# Organ.net
KiCad netlist of a schematic drawn in EAGLE
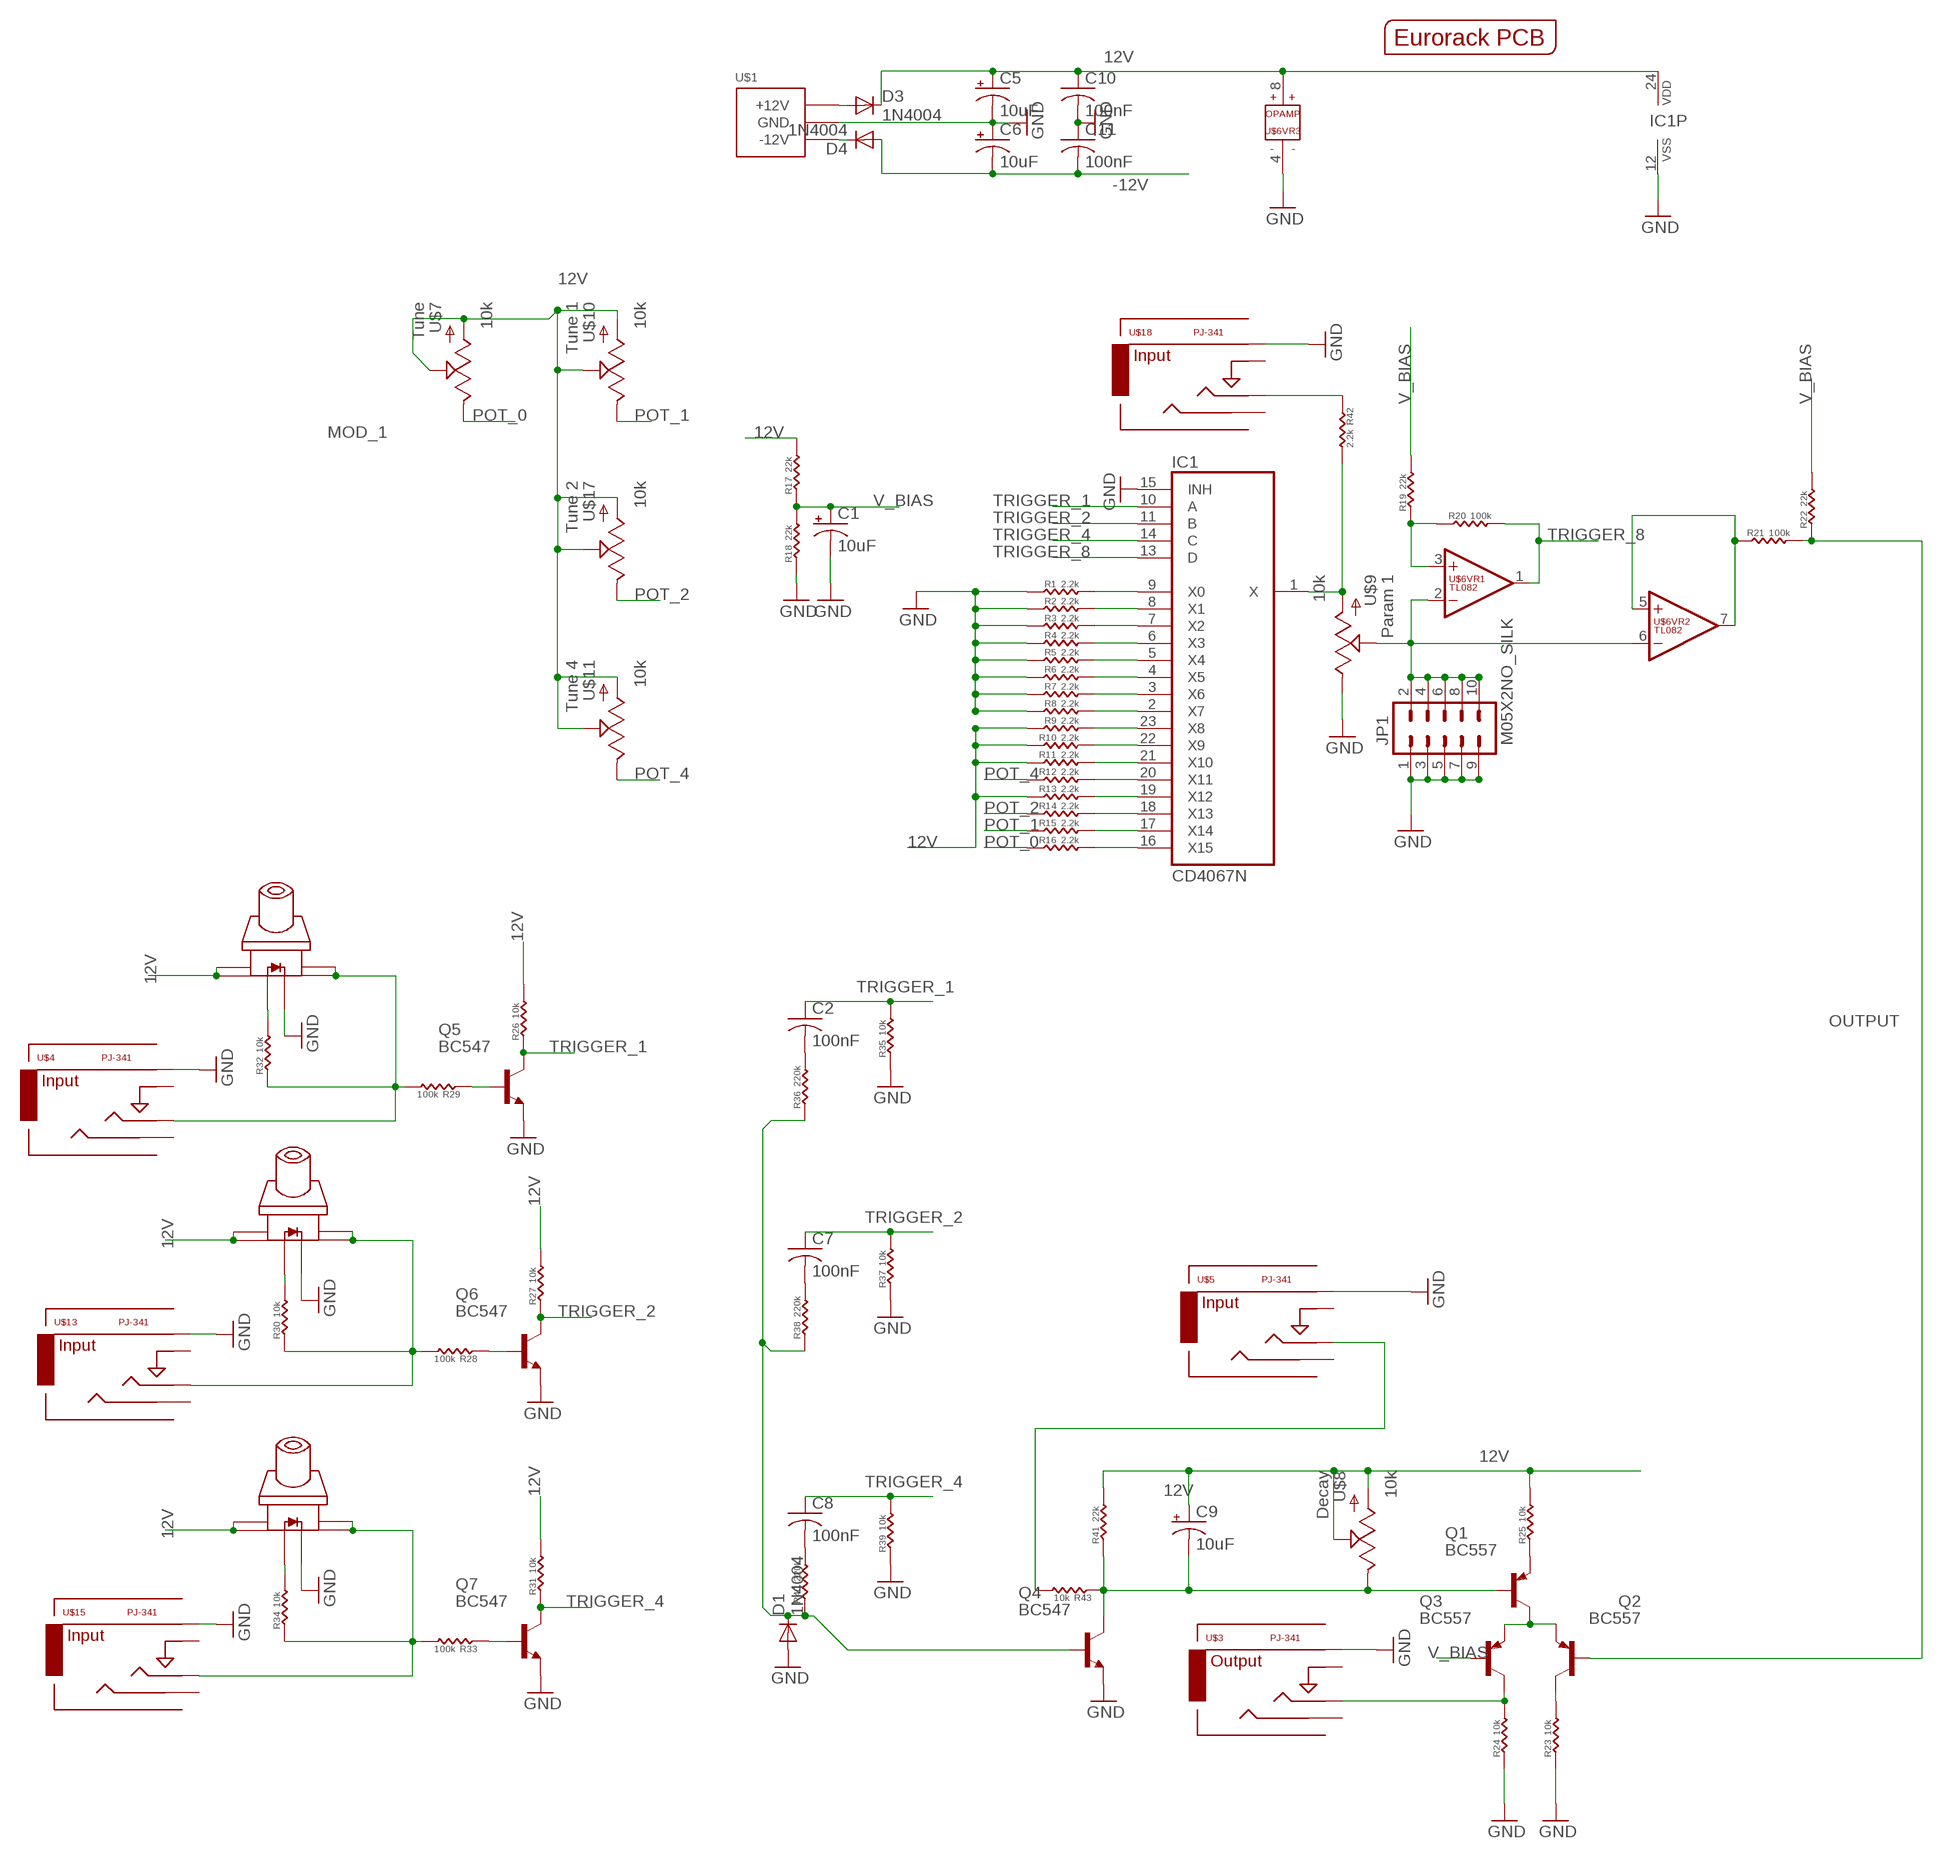
[diagram p0: schematic, sheet 1]

(export (version "E")
  (design (tool "Eeschema 10.0.6"))
  (components
    (comp (ref "C1")
      (value "10uF")
      (footprint "eagle-import:E5-6")
      (libsource (lib "eagle-import") (part "CPOL-USE5-6"))
    )
    (comp (ref "C2")
      (value "100nF")
      (footprint "eagle-import:C050-025X075")
      (libsource (lib "eagle-import") (part "C-US050-025X075"))
    )
    (comp (ref "C5")
      (value "10uF")
      (footprint "eagle-import:E5-6")
      (libsource (lib "eagle-import") (part "CPOL-USE5-6"))
    )
    (comp (ref "C6")
      (value "10uF")
      (footprint "eagle-import:E5-6")
      (libsource (lib "eagle-import") (part "CPOL-USE5-6"))
    )
    (comp (ref "C7")
      (value "100nF")
      (footprint "eagle-import:C050-025X075")
      (libsource (lib "eagle-import") (part "C-US050-025X075"))
    )
    (comp (ref "C8")
      (value "100nF")
      (footprint "eagle-import:C050-025X075")
      (libsource (lib "eagle-import") (part "C-US050-025X075"))
    )
    (comp (ref "C9")
      (value "10uF")
      (footprint "eagle-import:E5-6")
      (libsource (lib "eagle-import") (part "CPOL-USE5-6"))
    )
    (comp (ref "C10")
      (value "100nF")
      (footprint "eagle-import:C050-025X075")
      (libsource (lib "eagle-import") (part "C-US050-025X075"))
    )
    (comp (ref "C11")
      (value "100nF")
      (footprint "eagle-import:C050-025X075")
      (libsource (lib "eagle-import") (part "C-US050-025X075"))
    )
    (comp (ref "D1")
      (value "1N4004")
      (footprint "eagle-import:DO41-10")
      (libsource (lib "eagle-import") (part "1N4004"))
    )
    (comp (ref "D3")
      (value "1N4004")
      (footprint "eagle-import:DO41-10")
      (libsource (lib "eagle-import") (part "1N4004"))
    )
    (comp (ref "D4")
      (value "1N4004")
      (footprint "eagle-import:DO41-10")
      (libsource (lib "eagle-import") (part "1N4004"))
    )
    (comp (ref "IC1")
      (value "CD4067N")
      (footprint "eagle-import:DIL24-6")
      (libsource (lib "eagle-import") (part "4067N"))
    )
    (comp (ref "JP1")
      (value "M05X2NO_SILK")
      (footprint "eagle-import:2X5_NOSILK")
      (libsource (lib "eagle-import") (part "M05X2NO_SILK"))
    )
    (comp (ref "Q1")
      (value "BC557")
      (footprint "eagle-import:TO92")
      (libsource (lib "eagle-import") (part "BC557TO92"))
    )
    (comp (ref "Q2")
      (value "BC557")
      (footprint "eagle-import:TO92")
      (libsource (lib "eagle-import") (part "BC557TO92"))
    )
    (comp (ref "Q3")
      (value "BC557")
      (footprint "eagle-import:TO92")
      (libsource (lib "eagle-import") (part "BC557TO92"))
    )
    (comp (ref "Q4")
      (value "BC547")
      (footprint "eagle-import:TO92")
      (libsource (lib "eagle-import") (part "BC547"))
    )
    (comp (ref "Q5")
      (value "BC547")
      (footprint "eagle-import:TO92")
      (libsource (lib "eagle-import") (part "BC547"))
    )
    (comp (ref "Q6")
      (value "BC547")
      (footprint "eagle-import:TO92")
      (libsource (lib "eagle-import") (part "BC547"))
    )
    (comp (ref "Q7")
      (value "BC547")
      (footprint "eagle-import:TO92")
      (libsource (lib "eagle-import") (part "BC547"))
    )
    (comp (ref "R1")
      (value "2.2k")
      (footprint "eagle-import:0204_5")
      (libsource (lib "eagle-import") (part "R-US_0204/5"))
    )
    (comp (ref "R2")
      (value "2.2k")
      (footprint "eagle-import:0204_5")
      (libsource (lib "eagle-import") (part "R-US_0204/5"))
    )
    (comp (ref "R3")
      (value "2.2k")
      (footprint "eagle-import:0204_5")
      (libsource (lib "eagle-import") (part "R-US_0204/5"))
    )
    (comp (ref "R4")
      (value "2.2k")
      (footprint "eagle-import:0204_5")
      (libsource (lib "eagle-import") (part "R-US_0204/5"))
    )
    (comp (ref "R5")
      (value "2.2k")
      (footprint "eagle-import:0204_5")
      (libsource (lib "eagle-import") (part "R-US_0204/5"))
    )
    (comp (ref "R6")
      (value "2.2k")
      (footprint "eagle-import:0204_5")
      (libsource (lib "eagle-import") (part "R-US_0204/5"))
    )
    (comp (ref "R7")
      (value "2.2k")
      (footprint "eagle-import:0204_5")
      (libsource (lib "eagle-import") (part "R-US_0204/5"))
    )
    (comp (ref "R8")
      (value "2.2k")
      (footprint "eagle-import:0204_5")
      (libsource (lib "eagle-import") (part "R-US_0204/5"))
    )
    (comp (ref "R9")
      (value "2.2k")
      (footprint "eagle-import:0204_5")
      (libsource (lib "eagle-import") (part "R-US_0204/5"))
    )
    (comp (ref "R10")
      (value "2.2k")
      (footprint "eagle-import:0204_5")
      (libsource (lib "eagle-import") (part "R-US_0204/5"))
    )
    (comp (ref "R11")
      (value "2.2k")
      (footprint "eagle-import:0204_5")
      (libsource (lib "eagle-import") (part "R-US_0204/5"))
    )
    (comp (ref "R12")
      (value "2.2k")
      (footprint "eagle-import:0204_5")
      (libsource (lib "eagle-import") (part "R-US_0204/5"))
    )
    (comp (ref "R13")
      (value "2.2k")
      (footprint "eagle-import:0204_5")
      (libsource (lib "eagle-import") (part "R-US_0204/5"))
    )
    (comp (ref "R14")
      (value "2.2k")
      (footprint "eagle-import:0204_5")
      (libsource (lib "eagle-import") (part "R-US_0204/5"))
    )
    (comp (ref "R15")
      (value "2.2k")
      (footprint "eagle-import:0204_5")
      (libsource (lib "eagle-import") (part "R-US_0204/5"))
    )
    (comp (ref "R16")
      (value "2.2k")
      (footprint "eagle-import:0204_5")
      (libsource (lib "eagle-import") (part "R-US_0204/5"))
    )
    (comp (ref "R17")
      (value "22k")
      (footprint "eagle-import:0204_5")
      (libsource (lib "eagle-import") (part "R-US_0204/5"))
    )
    (comp (ref "R18")
      (value "22k")
      (footprint "eagle-import:0204_5")
      (libsource (lib "eagle-import") (part "R-US_0204/5"))
    )
    (comp (ref "R19")
      (value "22k")
      (footprint "eagle-import:0204_5")
      (libsource (lib "eagle-import") (part "R-US_0204/5"))
    )
    (comp (ref "R20")
      (value "100k")
      (footprint "eagle-import:0204_5")
      (libsource (lib "eagle-import") (part "R-US_0204/5"))
    )
    (comp (ref "R21")
      (value "100k")
      (footprint "eagle-import:0204_5")
      (libsource (lib "eagle-import") (part "R-US_0204/5"))
    )
    (comp (ref "R22")
      (value "22k")
      (footprint "eagle-import:0204_5")
      (libsource (lib "eagle-import") (part "R-US_0204/5"))
    )
    (comp (ref "R23")
      (value "10k")
      (footprint "eagle-import:0204_5")
      (libsource (lib "eagle-import") (part "R-US_0204/5"))
    )
    (comp (ref "R24")
      (value "10k")
      (footprint "eagle-import:0204_5")
      (libsource (lib "eagle-import") (part "R-US_0204/5"))
    )
    (comp (ref "R25")
      (value "10k")
      (footprint "eagle-import:0204_5")
      (libsource (lib "eagle-import") (part "R-US_0204/5"))
    )
    (comp (ref "R26")
      (value "10k")
      (footprint "eagle-import:0204_5")
      (libsource (lib "eagle-import") (part "R-US_0204/5"))
    )
    (comp (ref "R27")
      (value "10k")
      (footprint "eagle-import:0204_5")
      (libsource (lib "eagle-import") (part "R-US_0204/5"))
    )
    (comp (ref "R28")
      (value "100k")
      (footprint "eagle-import:0204_5")
      (libsource (lib "eagle-import") (part "R-US_0204/5"))
    )
    (comp (ref "R29")
      (value "100k")
      (footprint "eagle-import:0204_5")
      (libsource (lib "eagle-import") (part "R-US_0204/5"))
    )
    (comp (ref "R30")
      (value "10k")
      (footprint "eagle-import:0204_5")
      (libsource (lib "eagle-import") (part "R-US_0204/5"))
    )
    (comp (ref "R31")
      (value "10k")
      (footprint "eagle-import:0204_5")
      (libsource (lib "eagle-import") (part "R-US_0204/5"))
    )
    (comp (ref "R32")
      (value "10k")
      (footprint "eagle-import:0204_5")
      (libsource (lib "eagle-import") (part "R-US_0204/5"))
    )
    (comp (ref "R33")
      (value "100k")
      (footprint "eagle-import:0204_5")
      (libsource (lib "eagle-import") (part "R-US_0204/5"))
    )
    (comp (ref "R34")
      (value "10k")
      (footprint "eagle-import:0204_5")
      (libsource (lib "eagle-import") (part "R-US_0204/5"))
    )
    (comp (ref "R35")
      (value "10k")
      (footprint "eagle-import:0204_5")
      (libsource (lib "eagle-import") (part "R-US_0204/5"))
    )
    (comp (ref "R36")
      (value "220k")
      (footprint "eagle-import:0204_5")
      (libsource (lib "eagle-import") (part "R-US_0204/5"))
    )
    (comp (ref "R37")
      (value "10k")
      (footprint "eagle-import:0204_5")
      (libsource (lib "eagle-import") (part "R-US_0204/5"))
    )
    (comp (ref "R38")
      (value "220k")
      (footprint "eagle-import:0204_5")
      (libsource (lib "eagle-import") (part "R-US_0204/5"))
    )
    (comp (ref "R39")
      (value "10k")
      (footprint "eagle-import:0204_5")
      (libsource (lib "eagle-import") (part "R-US_0204/5"))
    )
    (comp (ref "R40")
      (value "220k")
      (footprint "eagle-import:0204_5")
      (libsource (lib "eagle-import") (part "R-US_0204/5"))
    )
    (comp (ref "R41")
      (value "22k")
      (footprint "eagle-import:0204_5")
      (libsource (lib "eagle-import") (part "R-US_0204/5"))
    )
    (comp (ref "R42")
      (value "2.2k")
      (footprint "eagle-import:0204_5")
      (libsource (lib "eagle-import") (part "R-US_0204/5"))
    )
    (comp (ref "R43")
      (value "10k")
      (footprint "eagle-import:0204_5")
      (libsource (lib "eagle-import") (part "R-US_0204/5"))
    )
    (comp (ref "U$1")
      (value "POWER_SIMPLE10")
      (footprint "eagle-import:POWER_10")
      (libsource (lib "eagle-import") (part "POWER_SIMPLE10"))
    )
    (comp (ref "U$2")
      (value "EURORACK_PCB12HP")
      (footprint "eagle-import:EURORACK12HPPCB")
      (libsource (lib "eagle-import") (part "EURORACK_PCB12HP"))
    )
    (comp (ref "U$3")
      (value "PJ-341")
      (footprint "eagle-import:3.5MM-JACK-SWITCH-13MM-OUTPUT")
      (libsource (lib "eagle-import") (part "AUDIO-JACKOUTPUT"))
    )
    (comp (ref "U$4")
      (value "PJ-341")
      (footprint "eagle-import:3.5MM-JACK-SWITCH-13MM-INPUT")
      (libsource (lib "eagle-import") (part "AUDIO-JACKINPUT"))
    )
    (comp (ref "U$5")
      (value "PJ-341")
      (footprint "eagle-import:3.5MM-JACK-SWITCH-13MM-INPUT")
      (libsource (lib "eagle-import") (part "AUDIO-JACKINPUT"))
    )
    (comp (ref "U$6")
      (value "TL082")
      (footprint "eagle-import:DIL08")
      (libsource (lib "eagle-import") (part "TL072DIP"))
    )
    (comp (ref "U$7")
      (value "10k")
      (footprint "eagle-import:OG-POTS_ALPS_POT_VERTICAL")
      (fields (field (name "DESC") "Tune"))
      (libsource (lib "eagle-import") (part "POTZEPHPOT"))
    )
    (comp (ref "U$8")
      (value "10k")
      (footprint "eagle-import:OG-POTS_ALPS_POT_VERTICAL")
      (fields (field (name "DESC") "Decay"))
      (libsource (lib "eagle-import") (part "POTZEPHPOT"))
    )
    (comp (ref "U$9")
      (value "10k")
      (footprint "eagle-import:OG-POTS_ALPS_POT_VERTICAL")
      (fields (field (name "DESC") "Param 1"))
      (libsource (lib "eagle-import") (part "POTZEPHPOT"))
    )
    (comp (ref "U$10")
      (value "10k")
      (footprint "eagle-import:OG-POTS_ALPS_POT_VERTICAL")
      (fields (field (name "DESC") "Tune 1"))
      (libsource (lib "eagle-import") (part "POTZEPHPOT"))
    )
    (comp (ref "U$11")
      (value "10k")
      (footprint "eagle-import:OG-POTS_ALPS_POT_VERTICAL")
      (fields (field (name "DESC") "Tune 4"))
      (libsource (lib "eagle-import") (part "POTZEPHPOT"))
    )
    (comp (ref "U$12")
      (value "SWITCH_W_LED_PB6149L-X-102YELLOW")
      (footprint "eagle-import:PB6149L")
      (libsource (lib "eagle-import") (part "SWITCH_W_LED_PB6149L-X-102YELLOW"))
    )
    (comp (ref "U$13")
      (value "PJ-341")
      (footprint "eagle-import:3.5MM-JACK-SWITCH-13MM-INPUT")
      (libsource (lib "eagle-import") (part "AUDIO-JACKINPUT"))
    )
    (comp (ref "U$14")
      (value "SWITCH_W_LED_PB6149L-X-102YELLOW")
      (footprint "eagle-import:PB6149L")
      (libsource (lib "eagle-import") (part "SWITCH_W_LED_PB6149L-X-102YELLOW"))
    )
    (comp (ref "U$15")
      (value "PJ-341")
      (footprint "eagle-import:3.5MM-JACK-SWITCH-13MM-INPUT")
      (libsource (lib "eagle-import") (part "AUDIO-JACKINPUT"))
    )
    (comp (ref "U$16")
      (value "SWITCH_W_LED_PB6149L-X-102YELLOW")
      (footprint "eagle-import:PB6149L")
      (libsource (lib "eagle-import") (part "SWITCH_W_LED_PB6149L-X-102YELLOW"))
    )
    (comp (ref "U$17")
      (value "10k")
      (footprint "eagle-import:OG-POTS_ALPS_POT_VERTICAL")
      (fields (field (name "DESC") "Tune 2"))
      (libsource (lib "eagle-import") (part "POTZEPHPOT"))
    )
    (comp (ref "U$18")
      (value "PJ-341")
      (footprint "eagle-import:3.5MM-JACK-SWITCH-13MM-INPUT")
      (libsource (lib "eagle-import") (part "AUDIO-JACKINPUT"))
    )
  )
  (nets
    (net (code "1") (name "/-12V") (class "Default")
      (node (ref "C11") (pin "2") (pinfunction "2_2") (pintype "passive"))
      (node (ref "C6") (pin "-") (pinfunction "-_-") (pintype "passive"))
      (node (ref "D4") (pin "A") (pinfunction "A_A") (pintype "passive"))
    )
    (net (code "2") (name "/12V") (class "Default")
      (node (ref "C10") (pin "1") (pinfunction "1_1") (pintype "passive"))
      (node (ref "C5") (pin "+") (pinfunction "+_+") (pintype "passive"))
      (node (ref "C9") (pin "+") (pinfunction "+_+") (pintype "passive"))
      (node (ref "D3") (pin "C") (pinfunction "C_C") (pintype "passive"))
      (node (ref "IC1") (pin "24") (pinfunction "VDD_24") (pintype "power_in"))
      (node (ref "R10") (pin "1") (pinfunction "1_1") (pintype "passive"))
      (node (ref "R11") (pin "1") (pinfunction "1_1") (pintype "passive"))
      (node (ref "R13") (pin "1") (pinfunction "1_1") (pintype "passive"))
      (node (ref "R17") (pin "2") (pinfunction "2_2") (pintype "passive"))
      (node (ref "R25") (pin "2") (pinfunction "2_2") (pintype "passive"))
      (node (ref "R26") (pin "2") (pinfunction "2_2") (pintype "passive"))
      (node (ref "R27") (pin "2") (pinfunction "2_2") (pintype "passive"))
      (node (ref "R31") (pin "2") (pinfunction "2_2") (pintype "passive"))
      (node (ref "R41") (pin "2") (pinfunction "2_2") (pintype "passive"))
      (node (ref "R9") (pin "1") (pinfunction "1_1") (pintype "passive"))
      (node (ref "U$10") (pin "P$2") (pinfunction "S_P$2") (pintype "passive"))
      (node (ref "U$10") (pin "P$3") (pinfunction "A_P$3") (pintype "passive"))
      (node (ref "U$11") (pin "P$2") (pinfunction "S_P$2") (pintype "passive"))
      (node (ref "U$11") (pin "P$3") (pinfunction "A_P$3") (pintype "passive"))
      (node (ref "U$12") (pin "1") (pinfunction "1_1") (pintype "bidirectional"))
      (node (ref "U$12") (pin "2") (pinfunction "2_2") (pintype "bidirectional"))
      (node (ref "U$14") (pin "1") (pinfunction "1_1") (pintype "bidirectional"))
      (node (ref "U$14") (pin "2") (pinfunction "2_2") (pintype "bidirectional"))
      (node (ref "U$16") (pin "1") (pinfunction "1_1") (pintype "bidirectional"))
      (node (ref "U$16") (pin "2") (pinfunction "2_2") (pintype "bidirectional"))
      (node (ref "U$17") (pin "P$2") (pinfunction "S_P$2") (pintype "passive"))
      (node (ref "U$17") (pin "P$3") (pinfunction "A_P$3") (pintype "passive"))
      (node (ref "U$6") (pin "8") (pinfunction "V+_8") (pintype "power_in"))
      (node (ref "U$7") (pin "P$2") (pinfunction "S_P$2") (pintype "passive"))
      (node (ref "U$7") (pin "P$3") (pinfunction "A_P$3") (pintype "passive"))
      (node (ref "U$8") (pin "P$2") (pinfunction "S_P$2") (pintype "passive"))
      (node (ref "U$8") (pin "P$3") (pinfunction "A_P$3") (pintype "passive"))
    )
    (net (code "3") (name "/MOD_1") (class "Default")
      (node (ref "IC1") (pin "1") (pinfunction "X_1") (pintype "output"))
      (node (ref "R42") (pin "2") (pinfunction "2_2") (pintype "passive"))
      (node (ref "U$9") (pin "P$3") (pinfunction "A_P$3") (pintype "passive"))
    )
    (net (code "4") (name "/OUTPUT") (class "Default")
      (node (ref "Q2") (pin "2") (pinfunction "B_2") (pintype "passive"))
      (node (ref "R21") (pin "2") (pinfunction "2_2") (pintype "passive"))
      (node (ref "R22") (pin "1") (pinfunction "1_1") (pintype "passive"))
    )
    (net (code "5") (name "/POT_0") (class "Default")
      (node (ref "R16") (pin "1") (pinfunction "1_1") (pintype "passive"))
      (node (ref "U$7") (pin "P$1") (pinfunction "E_P$1") (pintype "passive"))
    )
    (net (code "6") (name "/POT_1") (class "Default")
      (node (ref "R15") (pin "1") (pinfunction "1_1") (pintype "passive"))
      (node (ref "U$10") (pin "P$1") (pinfunction "E_P$1") (pintype "passive"))
    )
    (net (code "7") (name "/POT_2") (class "Default")
      (node (ref "R14") (pin "1") (pinfunction "1_1") (pintype "passive"))
      (node (ref "U$17") (pin "P$1") (pinfunction "E_P$1") (pintype "passive"))
    )
    (net (code "8") (name "/POT_4") (class "Default")
      (node (ref "R12") (pin "1") (pinfunction "1_1") (pintype "passive"))
      (node (ref "U$11") (pin "P$1") (pinfunction "E_P$1") (pintype "passive"))
    )
    (net (code "9") (name "/TRIGGER_1") (class "Default")
      (node (ref "C2") (pin "1") (pinfunction "1_1") (pintype "passive"))
      (node (ref "IC1") (pin "10") (pinfunction "A_10") (pintype "input"))
      (node (ref "Q5") (pin "3") (pinfunction "C_3") (pintype "passive"))
      (node (ref "R26") (pin "1") (pinfunction "1_1") (pintype "passive"))
      (node (ref "R35") (pin "2") (pinfunction "2_2") (pintype "passive"))
    )
    (net (code "10") (name "/TRIGGER_2") (class "Default")
      (node (ref "C7") (pin "1") (pinfunction "1_1") (pintype "passive"))
      (node (ref "IC1") (pin "11") (pinfunction "B_11") (pintype "input"))
      (node (ref "Q6") (pin "3") (pinfunction "C_3") (pintype "passive"))
      (node (ref "R27") (pin "1") (pinfunction "1_1") (pintype "passive"))
      (node (ref "R37") (pin "2") (pinfunction "2_2") (pintype "passive"))
    )
    (net (code "11") (name "/TRIGGER_4") (class "Default")
      (node (ref "C8") (pin "1") (pinfunction "1_1") (pintype "passive"))
      (node (ref "IC1") (pin "14") (pinfunction "C_14") (pintype "input"))
      (node (ref "Q7") (pin "3") (pinfunction "C_3") (pintype "passive"))
      (node (ref "R31") (pin "1") (pinfunction "1_1") (pintype "passive"))
      (node (ref "R39") (pin "2") (pinfunction "2_2") (pintype "passive"))
    )
    (net (code "12") (name "/TRIGGER_8") (class "Default")
      (node (ref "IC1") (pin "13") (pinfunction "D_13") (pintype "input"))
      (node (ref "R20") (pin "2") (pinfunction "2_2") (pintype "passive"))
      (node (ref "U$6") (pin "1") (pinfunction "OUT_1") (pintype "output"))
    )
    (net (code "13") (name "/V_BIAS") (class "Default")
      (node (ref "C1") (pin "+") (pinfunction "+_+") (pintype "passive"))
      (node (ref "Q3") (pin "2") (pinfunction "B_2") (pintype "passive"))
      (node (ref "R17") (pin "1") (pinfunction "1_1") (pintype "passive"))
      (node (ref "R18") (pin "2") (pinfunction "2_2") (pintype "passive"))
      (node (ref "R19") (pin "2") (pinfunction "2_2") (pintype "passive"))
      (node (ref "R22") (pin "2") (pinfunction "2_2") (pintype "passive"))
    )
    (net (code "14") (name "GND") (class "Default")
      (node (ref "C1") (pin "-") (pinfunction "-_-") (pintype "passive"))
      (node (ref "C10") (pin "2") (pinfunction "2_2") (pintype "passive"))
      (node (ref "C11") (pin "1") (pinfunction "1_1") (pintype "passive"))
      (node (ref "C5") (pin "-") (pinfunction "-_-") (pintype "passive"))
      (node (ref "C6") (pin "+") (pinfunction "+_+") (pintype "passive"))
      (node (ref "D1") (pin "A") (pinfunction "A_A") (pintype "passive"))
      (node (ref "IC1") (pin "12") (pinfunction "VSS_12") (pintype "power_in"))
      (node (ref "IC1") (pin "15") (pinfunction "INH_15") (pintype "input"))
      (node (ref "JP1") (pin "1") (pinfunction "1_1") (pintype "passive"))
      (node (ref "JP1") (pin "3") (pinfunction "3_3") (pintype "passive"))
      (node (ref "JP1") (pin "5") (pinfunction "5_5") (pintype "passive"))
      (node (ref "JP1") (pin "7") (pinfunction "7_7") (pintype "passive"))
      (node (ref "JP1") (pin "9") (pinfunction "9_9") (pintype "passive"))
      (node (ref "Q4") (pin "1") (pinfunction "E_1") (pintype "passive"))
      (node (ref "Q5") (pin "1") (pinfunction "E_1") (pintype "passive"))
      (node (ref "Q6") (pin "1") (pinfunction "E_1") (pintype "passive"))
      (node (ref "Q7") (pin "1") (pinfunction "E_1") (pintype "passive"))
      (node (ref "R1") (pin "1") (pinfunction "1_1") (pintype "passive"))
      (node (ref "R18") (pin "1") (pinfunction "1_1") (pintype "passive"))
      (node (ref "R2") (pin "1") (pinfunction "1_1") (pintype "passive"))
      (node (ref "R23") (pin "1") (pinfunction "1_1") (pintype "passive"))
      (node (ref "R24") (pin "1") (pinfunction "1_1") (pintype "passive"))
      (node (ref "R3") (pin "1") (pinfunction "1_1") (pintype "passive"))
      (node (ref "R35") (pin "1") (pinfunction "1_1") (pintype "passive"))
      (node (ref "R37") (pin "1") (pinfunction "1_1") (pintype "passive"))
      (node (ref "R39") (pin "1") (pinfunction "1_1") (pintype "passive"))
      (node (ref "R4") (pin "1") (pinfunction "1_1") (pintype "passive"))
      (node (ref "R5") (pin "1") (pinfunction "1_1") (pintype "passive"))
      (node (ref "R6") (pin "1") (pinfunction "1_1") (pintype "passive"))
      (node (ref "R7") (pin "1") (pinfunction "1_1") (pintype "passive"))
      (node (ref "R8") (pin "1") (pinfunction "1_1") (pintype "passive"))
      (node (ref "U$1") (pin "3") (pinfunction "GND_3") (pintype "bidirectional"))
      (node (ref "U$1") (pin "4") (pinfunction "GND_4") (pintype "bidirectional"))
      (node (ref "U$1") (pin "5") (pinfunction "GND_5") (pintype "bidirectional"))
      (node (ref "U$1") (pin "6") (pinfunction "GND_6") (pintype "bidirectional"))
      (node (ref "U$1") (pin "7") (pinfunction "GND_7") (pintype "bidirectional"))
      (node (ref "U$1") (pin "8") (pinfunction "GND_8") (pintype "bidirectional"))
      (node (ref "U$12") (pin "LEDNEG") (pinfunction "NEG_LEDNEG") (pintype "bidirectional"))
      (node (ref "U$13") (pin "RING@3") (pinfunction "RING_RING@3") (pintype "bidirectional"))
      (node (ref "U$14") (pin "LEDNEG") (pinfunction "NEG_LEDNEG") (pintype "bidirectional"))
      (node (ref "U$15") (pin "RING@3") (pinfunction "RING_RING@3") (pintype "bidirectional"))
      (node (ref "U$16") (pin "LEDNEG") (pinfunction "NEG_LEDNEG") (pintype "bidirectional"))
      (node (ref "U$18") (pin "RING@3") (pinfunction "RING_RING@3") (pintype "bidirectional"))
      (node (ref "U$3") (pin "RING@3") (pinfunction "RING_RING@3") (pintype "bidirectional"))
      (node (ref "U$4") (pin "RING@3") (pinfunction "RING_RING@3") (pintype "bidirectional"))
      (node (ref "U$5") (pin "RING@3") (pinfunction "RING_RING@3") (pintype "bidirectional"))
      (node (ref "U$6") (pin "4") (pinfunction "V-_4") (pintype "power_in"))
      (node (ref "U$9") (pin "P$1") (pinfunction "E_P$1") (pintype "passive"))
    )
    (net (code "15") (name "Net-(C2-Pad2)") (class "Default")
      (node (ref "C2") (pin "2") (pinfunction "2_2") (pintype "passive"))
      (node (ref "R36") (pin "2") (pinfunction "2_2") (pintype "passive"))
    )
    (net (code "16") (name "Net-(C7-Pad2)") (class "Default")
      (node (ref "C7") (pin "2") (pinfunction "2_2") (pintype "passive"))
      (node (ref "R38") (pin "2") (pinfunction "2_2") (pintype "passive"))
    )
    (net (code "17") (name "Net-(C8-Pad2)") (class "Default")
      (node (ref "C8") (pin "2") (pinfunction "2_2") (pintype "passive"))
      (node (ref "R40") (pin "2") (pinfunction "2_2") (pintype "passive"))
    )
    (net (code "18") (name "Net-(D3-PadA)") (class "Default")
      (node (ref "D3") (pin "A") (pinfunction "A_A") (pintype "passive"))
      (node (ref "U$1") (pin "10") (pinfunction "+12V_10") (pintype "bidirectional"))
      (node (ref "U$1") (pin "9") (pinfunction "+12V_9") (pintype "bidirectional"))
    )
    (net (code "19") (name "Net-(D4-PadC)") (class "Default")
      (node (ref "D4") (pin "C") (pinfunction "C_C") (pintype "passive"))
      (node (ref "U$1") (pin "1") (pinfunction "-12V_1") (pintype "bidirectional"))
      (node (ref "U$1") (pin "2") (pinfunction "-12V_2") (pintype "bidirectional"))
    )
    (net (code "20") (name "Net-(IC1A-X0)") (class "Default")
      (node (ref "IC1") (pin "9") (pinfunction "X0_9") (pintype "input"))
      (node (ref "R1") (pin "2") (pinfunction "2_2") (pintype "passive"))
    )
    (net (code "21") (name "Net-(IC1A-X1)") (class "Default")
      (node (ref "IC1") (pin "8") (pinfunction "X1_8") (pintype "input"))
      (node (ref "R2") (pin "2") (pinfunction "2_2") (pintype "passive"))
    )
    (net (code "22") (name "Net-(IC1A-X2)") (class "Default")
      (node (ref "IC1") (pin "7") (pinfunction "X2_7") (pintype "input"))
      (node (ref "R3") (pin "2") (pinfunction "2_2") (pintype "passive"))
    )
    (net (code "23") (name "Net-(IC1A-X3)") (class "Default")
      (node (ref "IC1") (pin "6") (pinfunction "X3_6") (pintype "input"))
      (node (ref "R4") (pin "2") (pinfunction "2_2") (pintype "passive"))
    )
    (net (code "24") (name "Net-(IC1A-X4)") (class "Default")
      (node (ref "IC1") (pin "5") (pinfunction "X4_5") (pintype "input"))
      (node (ref "R5") (pin "2") (pinfunction "2_2") (pintype "passive"))
    )
    (net (code "25") (name "Net-(IC1A-X5)") (class "Default")
      (node (ref "IC1") (pin "4") (pinfunction "X5_4") (pintype "input"))
      (node (ref "R6") (pin "2") (pinfunction "2_2") (pintype "passive"))
    )
    (net (code "26") (name "Net-(IC1A-X6)") (class "Default")
      (node (ref "IC1") (pin "3") (pinfunction "X6_3") (pintype "input"))
      (node (ref "R7") (pin "2") (pinfunction "2_2") (pintype "passive"))
    )
    (net (code "27") (name "Net-(IC1A-X7)") (class "Default")
      (node (ref "IC1") (pin "2") (pinfunction "X7_2") (pintype "input"))
      (node (ref "R8") (pin "2") (pinfunction "2_2") (pintype "passive"))
    )
    (net (code "28") (name "Net-(IC1A-X8)") (class "Default")
      (node (ref "IC1") (pin "23") (pinfunction "X8_23") (pintype "input"))
      (node (ref "R9") (pin "2") (pinfunction "2_2") (pintype "passive"))
    )
    (net (code "29") (name "Net-(IC1A-X9)") (class "Default")
      (node (ref "IC1") (pin "22") (pinfunction "X9_22") (pintype "input"))
      (node (ref "R10") (pin "2") (pinfunction "2_2") (pintype "passive"))
    )
    (net (code "30") (name "Net-(IC1A-X10)") (class "Default")
      (node (ref "IC1") (pin "21") (pinfunction "X10_21") (pintype "input"))
      (node (ref "R11") (pin "2") (pinfunction "2_2") (pintype "passive"))
    )
    (net (code "31") (name "Net-(IC1A-X11)") (class "Default")
      (node (ref "IC1") (pin "20") (pinfunction "X11_20") (pintype "input"))
      (node (ref "R12") (pin "2") (pinfunction "2_2") (pintype "passive"))
    )
    (net (code "32") (name "Net-(IC1A-X12)") (class "Default")
      (node (ref "IC1") (pin "19") (pinfunction "X12_19") (pintype "input"))
      (node (ref "R13") (pin "2") (pinfunction "2_2") (pintype "passive"))
    )
    (net (code "33") (name "Net-(IC1A-X13)") (class "Default")
      (node (ref "IC1") (pin "18") (pinfunction "X13_18") (pintype "input"))
      (node (ref "R14") (pin "2") (pinfunction "2_2") (pintype "passive"))
    )
    (net (code "34") (name "Net-(IC1A-X14)") (class "Default")
      (node (ref "IC1") (pin "17") (pinfunction "X14_17") (pintype "input"))
      (node (ref "R15") (pin "2") (pinfunction "2_2") (pintype "passive"))
    )
    (net (code "35") (name "Net-(IC1A-X15)") (class "Default")
      (node (ref "IC1") (pin "16") (pinfunction "X15_16") (pintype "input"))
      (node (ref "R16") (pin "2") (pinfunction "2_2") (pintype "passive"))
    )
    (net (code "36") (name "Net-(Q1-B)") (class "Default")
      (node (ref "C9") (pin "-") (pinfunction "-_-") (pintype "passive"))
      (node (ref "Q1") (pin "2") (pinfunction "B_2") (pintype "passive"))
      (node (ref "Q4") (pin "3") (pinfunction "C_3") (pintype "passive"))
      (node (ref "R41") (pin "1") (pinfunction "1_1") (pintype "passive"))
      (node (ref "R43") (pin "1") (pinfunction "1_1") (pintype "passive"))
      (node (ref "U$8") (pin "P$1") (pinfunction "E_P$1") (pintype "passive"))
    )
    (net (code "37") (name "Net-(Q1-C)") (class "Default")
      (node (ref "Q1") (pin "3") (pinfunction "C_3") (pintype "passive"))
      (node (ref "Q2") (pin "1") (pinfunction "E_1") (pintype "passive"))
      (node (ref "Q3") (pin "1") (pinfunction "E_1") (pintype "passive"))
    )
    (net (code "38") (name "Net-(Q1-E)") (class "Default")
      (node (ref "Q1") (pin "1") (pinfunction "E_1") (pintype "passive"))
      (node (ref "R25") (pin "1") (pinfunction "1_1") (pintype "passive"))
    )
    (net (code "39") (name "Net-(Q2-C)") (class "Default")
      (node (ref "Q2") (pin "3") (pinfunction "C_3") (pintype "passive"))
      (node (ref "R23") (pin "2") (pinfunction "2_2") (pintype "passive"))
    )
    (net (code "40") (name "Net-(Q3-C)") (class "Default")
      (node (ref "Q3") (pin "3") (pinfunction "C_3") (pintype "passive"))
      (node (ref "R24") (pin "2") (pinfunction "2_2") (pintype "passive"))
      (node (ref "U$3") (pin "TIP@3") (pinfunction "TIP_TIP@3") (pintype "bidirectional"))
    )
    (net (code "41") (name "Net-(Q4-B)") (class "Default")
      (node (ref "D1") (pin "C") (pinfunction "C_C") (pintype "passive"))
      (node (ref "Q4") (pin "2") (pinfunction "B_2") (pintype "passive"))
      (node (ref "R36") (pin "1") (pinfunction "1_1") (pintype "passive"))
      (node (ref "R38") (pin "1") (pinfunction "1_1") (pintype "passive"))
      (node (ref "R40") (pin "1") (pinfunction "1_1") (pintype "passive"))
    )
    (net (code "42") (name "Net-(Q5-B)") (class "Default")
      (node (ref "Q5") (pin "2") (pinfunction "B_2") (pintype "passive"))
      (node (ref "R29") (pin "1") (pinfunction "1_1") (pintype "passive"))
    )
    (net (code "43") (name "Net-(Q6-B)") (class "Default")
      (node (ref "Q6") (pin "2") (pinfunction "B_2") (pintype "passive"))
      (node (ref "R28") (pin "1") (pinfunction "1_1") (pintype "passive"))
    )
    (net (code "44") (name "Net-(Q7-B)") (class "Default")
      (node (ref "Q7") (pin "2") (pinfunction "B_2") (pintype "passive"))
      (node (ref "R33") (pin "1") (pinfunction "1_1") (pintype "passive"))
    )
    (net (code "45") (name "Net-(U$4-TIP)") (class "Default")
      (node (ref "R29") (pin "2") (pinfunction "2_2") (pintype "passive"))
      (node (ref "R32") (pin "1") (pinfunction "1_1") (pintype "passive"))
      (node (ref "U$12") (pin "3") (pinfunction "3_3") (pintype "bidirectional"))
      (node (ref "U$12") (pin "4") (pinfunction "4_4") (pintype "bidirectional"))
      (node (ref "U$4") (pin "TIP@3") (pinfunction "TIP_TIP@3") (pintype "bidirectional"))
    )
    (net (code "46") (name "Net-(U$5-TIP)") (class "Default")
      (node (ref "R43") (pin "2") (pinfunction "2_2") (pintype "passive"))
      (node (ref "U$5") (pin "TIP@3") (pinfunction "TIP_TIP@3") (pintype "bidirectional"))
    )
    (net (code "47") (name "Net-(U$6A-+IN)") (class "Default")
      (node (ref "R19") (pin "1") (pinfunction "1_1") (pintype "passive"))
      (node (ref "R20") (pin "1") (pinfunction "1_1") (pintype "passive"))
      (node (ref "U$6") (pin "3") (pinfunction "+IN_3") (pintype "input"))
    )
    (net (code "48") (name "Net-(U$6A--IN)") (class "Default")
      (node (ref "JP1") (pin "10") (pinfunction "10_10") (pintype "passive"))
      (node (ref "JP1") (pin "2") (pinfunction "2_2") (pintype "passive"))
      (node (ref "JP1") (pin "4") (pinfunction "4_4") (pintype "passive"))
      (node (ref "JP1") (pin "6") (pinfunction "6_6") (pintype "passive"))
      (node (ref "JP1") (pin "8") (pinfunction "8_8") (pintype "passive"))
      (node (ref "U$6") (pin "2") (pinfunction "-IN_2") (pintype "input"))
      (node (ref "U$6") (pin "6") (pinfunction "-IN_6") (pintype "input"))
      (node (ref "U$9") (pin "P$2") (pinfunction "S_P$2") (pintype "passive"))
    )
    (net (code "49") (name "Net-(U$6B-+IN)") (class "Default")
      (node (ref "R21") (pin "1") (pinfunction "1_1") (pintype "passive"))
      (node (ref "U$6") (pin "5") (pinfunction "+IN_5") (pintype "input"))
      (node (ref "U$6") (pin "7") (pinfunction "OUT_7") (pintype "output"))
    )
    (net (code "50") (name "Net-(U$12-POS)") (class "Default")
      (node (ref "R32") (pin "2") (pinfunction "2_2") (pintype "passive"))
      (node (ref "U$12") (pin "LEDPOS") (pinfunction "POS_LEDPOS") (pintype "bidirectional"))
    )
    (net (code "51") (name "Net-(U$13-TIP)") (class "Default")
      (node (ref "R28") (pin "2") (pinfunction "2_2") (pintype "passive"))
      (node (ref "R30") (pin "1") (pinfunction "1_1") (pintype "passive"))
      (node (ref "U$13") (pin "TIP@3") (pinfunction "TIP_TIP@3") (pintype "bidirectional"))
      (node (ref "U$14") (pin "3") (pinfunction "3_3") (pintype "bidirectional"))
      (node (ref "U$14") (pin "4") (pinfunction "4_4") (pintype "bidirectional"))
    )
    (net (code "52") (name "Net-(U$14-POS)") (class "Default")
      (node (ref "R30") (pin "2") (pinfunction "2_2") (pintype "passive"))
      (node (ref "U$14") (pin "LEDPOS") (pinfunction "POS_LEDPOS") (pintype "bidirectional"))
    )
    (net (code "53") (name "Net-(U$15-TIP)") (class "Default")
      (node (ref "R33") (pin "2") (pinfunction "2_2") (pintype "passive"))
      (node (ref "R34") (pin "1") (pinfunction "1_1") (pintype "passive"))
      (node (ref "U$15") (pin "TIP@3") (pinfunction "TIP_TIP@3") (pintype "bidirectional"))
      (node (ref "U$16") (pin "3") (pinfunction "3_3") (pintype "bidirectional"))
      (node (ref "U$16") (pin "4") (pinfunction "4_4") (pintype "bidirectional"))
    )
    (net (code "54") (name "Net-(U$16-POS)") (class "Default")
      (node (ref "R34") (pin "2") (pinfunction "2_2") (pintype "passive"))
      (node (ref "U$16") (pin "LEDPOS") (pinfunction "POS_LEDPOS") (pintype "bidirectional"))
    )
    (net (code "55") (name "Net-(U$18-TIP)") (class "Default")
      (node (ref "R42") (pin "1") (pinfunction "1_1") (pintype "passive"))
      (node (ref "U$18") (pin "TIP@3") (pinfunction "TIP_TIP@3") (pintype "bidirectional"))
    )
    (net (code "56") (name "unconnected-(U$3-SECOND-PadSECOND@3)") (class "Default")
      (node (ref "U$3") (pin "SECOND@3") (pinfunction "SECOND_SECOND@3") (pintype "bidirectional"))
    )
    (net (code "57") (name "unconnected-(U$3-SWITCH-PadSWITCH@3)") (class "Default")
      (node (ref "U$3") (pin "SWITCH@3") (pinfunction "SWITCH_SWITCH@3") (pintype "bidirectional"))
    )
    (net (code "58") (name "unconnected-(U$4-SECOND-PadSECOND@3)") (class "Default")
      (node (ref "U$4") (pin "SECOND@3") (pinfunction "SECOND_SECOND@3") (pintype "bidirectional"))
    )
    (net (code "59") (name "unconnected-(U$4-SWITCH-PadSWITCH@3)") (class "Default")
      (node (ref "U$4") (pin "SWITCH@3") (pinfunction "SWITCH_SWITCH@3") (pintype "bidirectional"))
    )
    (net (code "60") (name "unconnected-(U$5-SECOND-PadSECOND@3)") (class "Default")
      (node (ref "U$5") (pin "SECOND@3") (pinfunction "SECOND_SECOND@3") (pintype "bidirectional"))
    )
    (net (code "61") (name "unconnected-(U$5-SWITCH-PadSWITCH@3)") (class "Default")
      (node (ref "U$5") (pin "SWITCH@3") (pinfunction "SWITCH_SWITCH@3") (pintype "bidirectional"))
    )
    (net (code "62") (name "unconnected-(U$13-SECOND-PadSECOND@3)") (class "Default")
      (node (ref "U$13") (pin "SECOND@3") (pinfunction "SECOND_SECOND@3") (pintype "bidirectional"))
    )
    (net (code "63") (name "unconnected-(U$13-SWITCH-PadSWITCH@3)") (class "Default")
      (node (ref "U$13") (pin "SWITCH@3") (pinfunction "SWITCH_SWITCH@3") (pintype "bidirectional"))
    )
    (net (code "64") (name "unconnected-(U$15-SECOND-PadSECOND@3)") (class "Default")
      (node (ref "U$15") (pin "SECOND@3") (pinfunction "SECOND_SECOND@3") (pintype "bidirectional"))
    )
    (net (code "65") (name "unconnected-(U$15-SWITCH-PadSWITCH@3)") (class "Default")
      (node (ref "U$15") (pin "SWITCH@3") (pinfunction "SWITCH_SWITCH@3") (pintype "bidirectional"))
    )
    (net (code "66") (name "unconnected-(U$18-SECOND-PadSECOND@3)") (class "Default")
      (node (ref "U$18") (pin "SECOND@3") (pinfunction "SECOND_SECOND@3") (pintype "bidirectional"))
    )
    (net (code "67") (name "unconnected-(U$18-SWITCH-PadSWITCH@3)") (class "Default")
      (node (ref "U$18") (pin "SWITCH@3") (pinfunction "SWITCH_SWITCH@3") (pintype "bidirectional"))
    )
  )
)
